# Hilt-Side_Schematic.net
KiCad netlist of a schematic drawn in Altium Designer
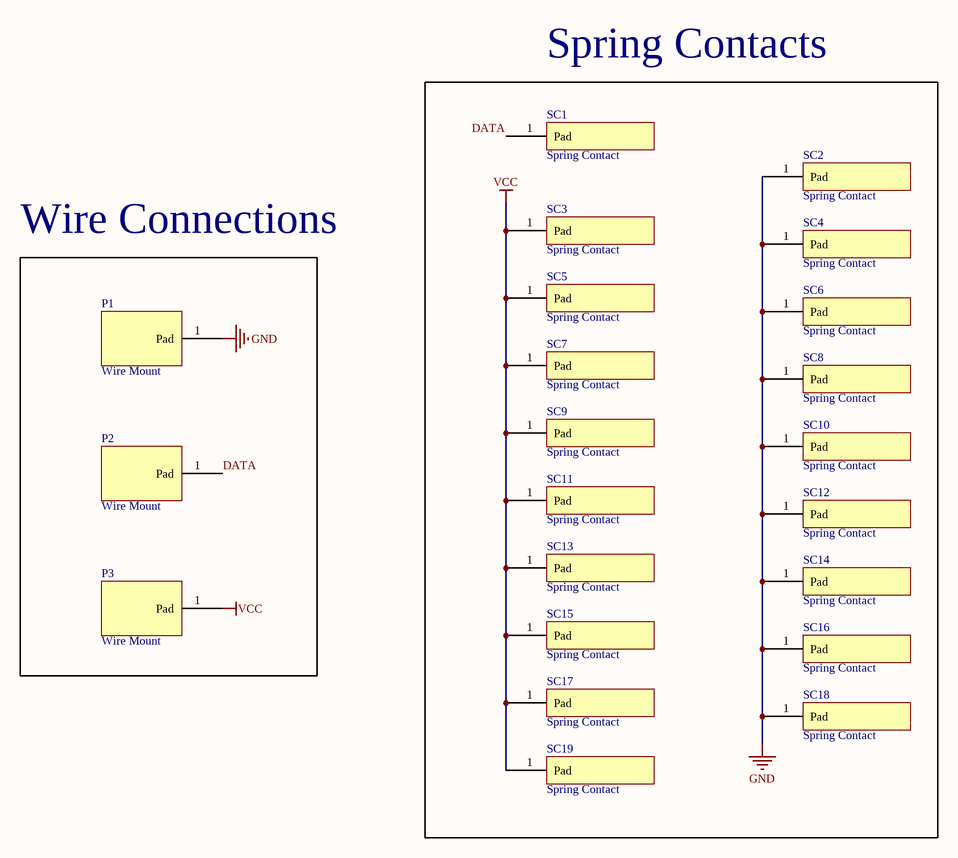
[diagram p0: Hilt-Side Schematic.SchDoc]

(export (version "E")
  (design (tool "Eeschema 10.0.6"))
  (components
    (comp (ref "P1")
      (value "Wire Mount")
      (footprint "Wire Mount")
      (libsource (lib "Lightsaber") (part "Wire Mount"))
    )
    (comp (ref "P2")
      (value "Wire Mount")
      (footprint "Wire Mount")
      (libsource (lib "Lightsaber") (part "Wire Mount"))
    )
    (comp (ref "P3")
      (value "Wire Mount")
      (footprint "Wire Mount")
      (libsource (lib "Lightsaber") (part "Wire Mount"))
    )
    (comp (ref "SC1")
      (value "Spring Contact")
      (footprint "Spring Contact")
      (libsource (lib "Lightsaber") (part "Spring Contact"))
    )
    (comp (ref "SC2")
      (value "Spring Contact")
      (footprint "Spring Contact")
      (libsource (lib "Lightsaber") (part "Spring Contact"))
    )
    (comp (ref "SC3")
      (value "Spring Contact")
      (footprint "Spring Contact")
      (libsource (lib "Lightsaber") (part "Spring Contact"))
    )
    (comp (ref "SC4")
      (value "Spring Contact")
      (footprint "Spring Contact")
      (libsource (lib "Lightsaber") (part "Spring Contact"))
    )
    (comp (ref "SC5")
      (value "Spring Contact")
      (footprint "Spring Contact")
      (libsource (lib "Lightsaber") (part "Spring Contact"))
    )
    (comp (ref "SC6")
      (value "Spring Contact")
      (footprint "Spring Contact")
      (libsource (lib "Lightsaber") (part "Spring Contact"))
    )
    (comp (ref "SC7")
      (value "Spring Contact")
      (footprint "Spring Contact")
      (libsource (lib "Lightsaber") (part "Spring Contact"))
    )
    (comp (ref "SC8")
      (value "Spring Contact")
      (footprint "Spring Contact")
      (libsource (lib "Lightsaber") (part "Spring Contact"))
    )
    (comp (ref "SC9")
      (value "Spring Contact")
      (footprint "Spring Contact")
      (libsource (lib "Lightsaber") (part "Spring Contact"))
    )
    (comp (ref "SC10")
      (value "Spring Contact")
      (footprint "Spring Contact")
      (libsource (lib "Lightsaber") (part "Spring Contact"))
    )
    (comp (ref "SC11")
      (value "Spring Contact")
      (footprint "Spring Contact")
      (libsource (lib "Lightsaber") (part "Spring Contact"))
    )
    (comp (ref "SC12")
      (value "Spring Contact")
      (footprint "Spring Contact")
      (libsource (lib "Lightsaber") (part "Spring Contact"))
    )
    (comp (ref "SC13")
      (value "Spring Contact")
      (footprint "Spring Contact")
      (libsource (lib "Lightsaber") (part "Spring Contact"))
    )
    (comp (ref "SC14")
      (value "Spring Contact")
      (footprint "Spring Contact")
      (libsource (lib "Lightsaber") (part "Spring Contact"))
    )
    (comp (ref "SC15")
      (value "Spring Contact")
      (footprint "Spring Contact")
      (libsource (lib "Lightsaber") (part "Spring Contact"))
    )
    (comp (ref "SC16")
      (value "Spring Contact")
      (footprint "Spring Contact")
      (libsource (lib "Lightsaber") (part "Spring Contact"))
    )
    (comp (ref "SC17")
      (value "Spring Contact")
      (footprint "Spring Contact")
      (libsource (lib "Lightsaber") (part "Spring Contact"))
    )
    (comp (ref "SC18")
      (value "Spring Contact")
      (footprint "Spring Contact")
      (libsource (lib "Lightsaber") (part "Spring Contact"))
    )
    (comp (ref "SC19")
      (value "Spring Contact")
      (footprint "Spring Contact")
      (libsource (lib "Lightsaber") (part "Spring Contact"))
    )
  )
  (nets
    (net (code "1") (name "/DATA") (class "Default")
      (node (ref "P2") (pin "1") (pinfunction "Pad_1") (pintype "passive"))
      (node (ref "SC1") (pin "1") (pinfunction "Pad_1") (pintype "passive"))
    )
    (net (code "2") (name "GND") (class "Default")
      (node (ref "P1") (pin "1") (pinfunction "Pad_1") (pintype "passive"))
      (node (ref "SC10") (pin "1") (pinfunction "Pad_1") (pintype "passive"))
      (node (ref "SC12") (pin "1") (pinfunction "Pad_1") (pintype "passive"))
      (node (ref "SC14") (pin "1") (pinfunction "Pad_1") (pintype "passive"))
      (node (ref "SC16") (pin "1") (pinfunction "Pad_1") (pintype "passive"))
      (node (ref "SC18") (pin "1") (pinfunction "Pad_1") (pintype "passive"))
      (node (ref "SC2") (pin "1") (pinfunction "Pad_1") (pintype "passive"))
      (node (ref "SC4") (pin "1") (pinfunction "Pad_1") (pintype "passive"))
      (node (ref "SC6") (pin "1") (pinfunction "Pad_1") (pintype "passive"))
      (node (ref "SC8") (pin "1") (pinfunction "Pad_1") (pintype "passive"))
    )
    (net (code "3") (name "VCC") (class "Default")
      (node (ref "P3") (pin "1") (pinfunction "Pad_1") (pintype "passive"))
      (node (ref "SC11") (pin "1") (pinfunction "Pad_1") (pintype "passive"))
      (node (ref "SC13") (pin "1") (pinfunction "Pad_1") (pintype "passive"))
      (node (ref "SC15") (pin "1") (pinfunction "Pad_1") (pintype "passive"))
      (node (ref "SC17") (pin "1") (pinfunction "Pad_1") (pintype "passive"))
      (node (ref "SC19") (pin "1") (pinfunction "Pad_1") (pintype "passive"))
      (node (ref "SC3") (pin "1") (pinfunction "Pad_1") (pintype "passive"))
      (node (ref "SC5") (pin "1") (pinfunction "Pad_1") (pintype "passive"))
      (node (ref "SC7") (pin "1") (pinfunction "Pad_1") (pintype "passive"))
      (node (ref "SC9") (pin "1") (pinfunction "Pad_1") (pintype "passive"))
    )
  )
)
